# ProPrj_tl494__2025-11-29.net
KiCad netlist of a schematic drawn in EasyEDA Pro
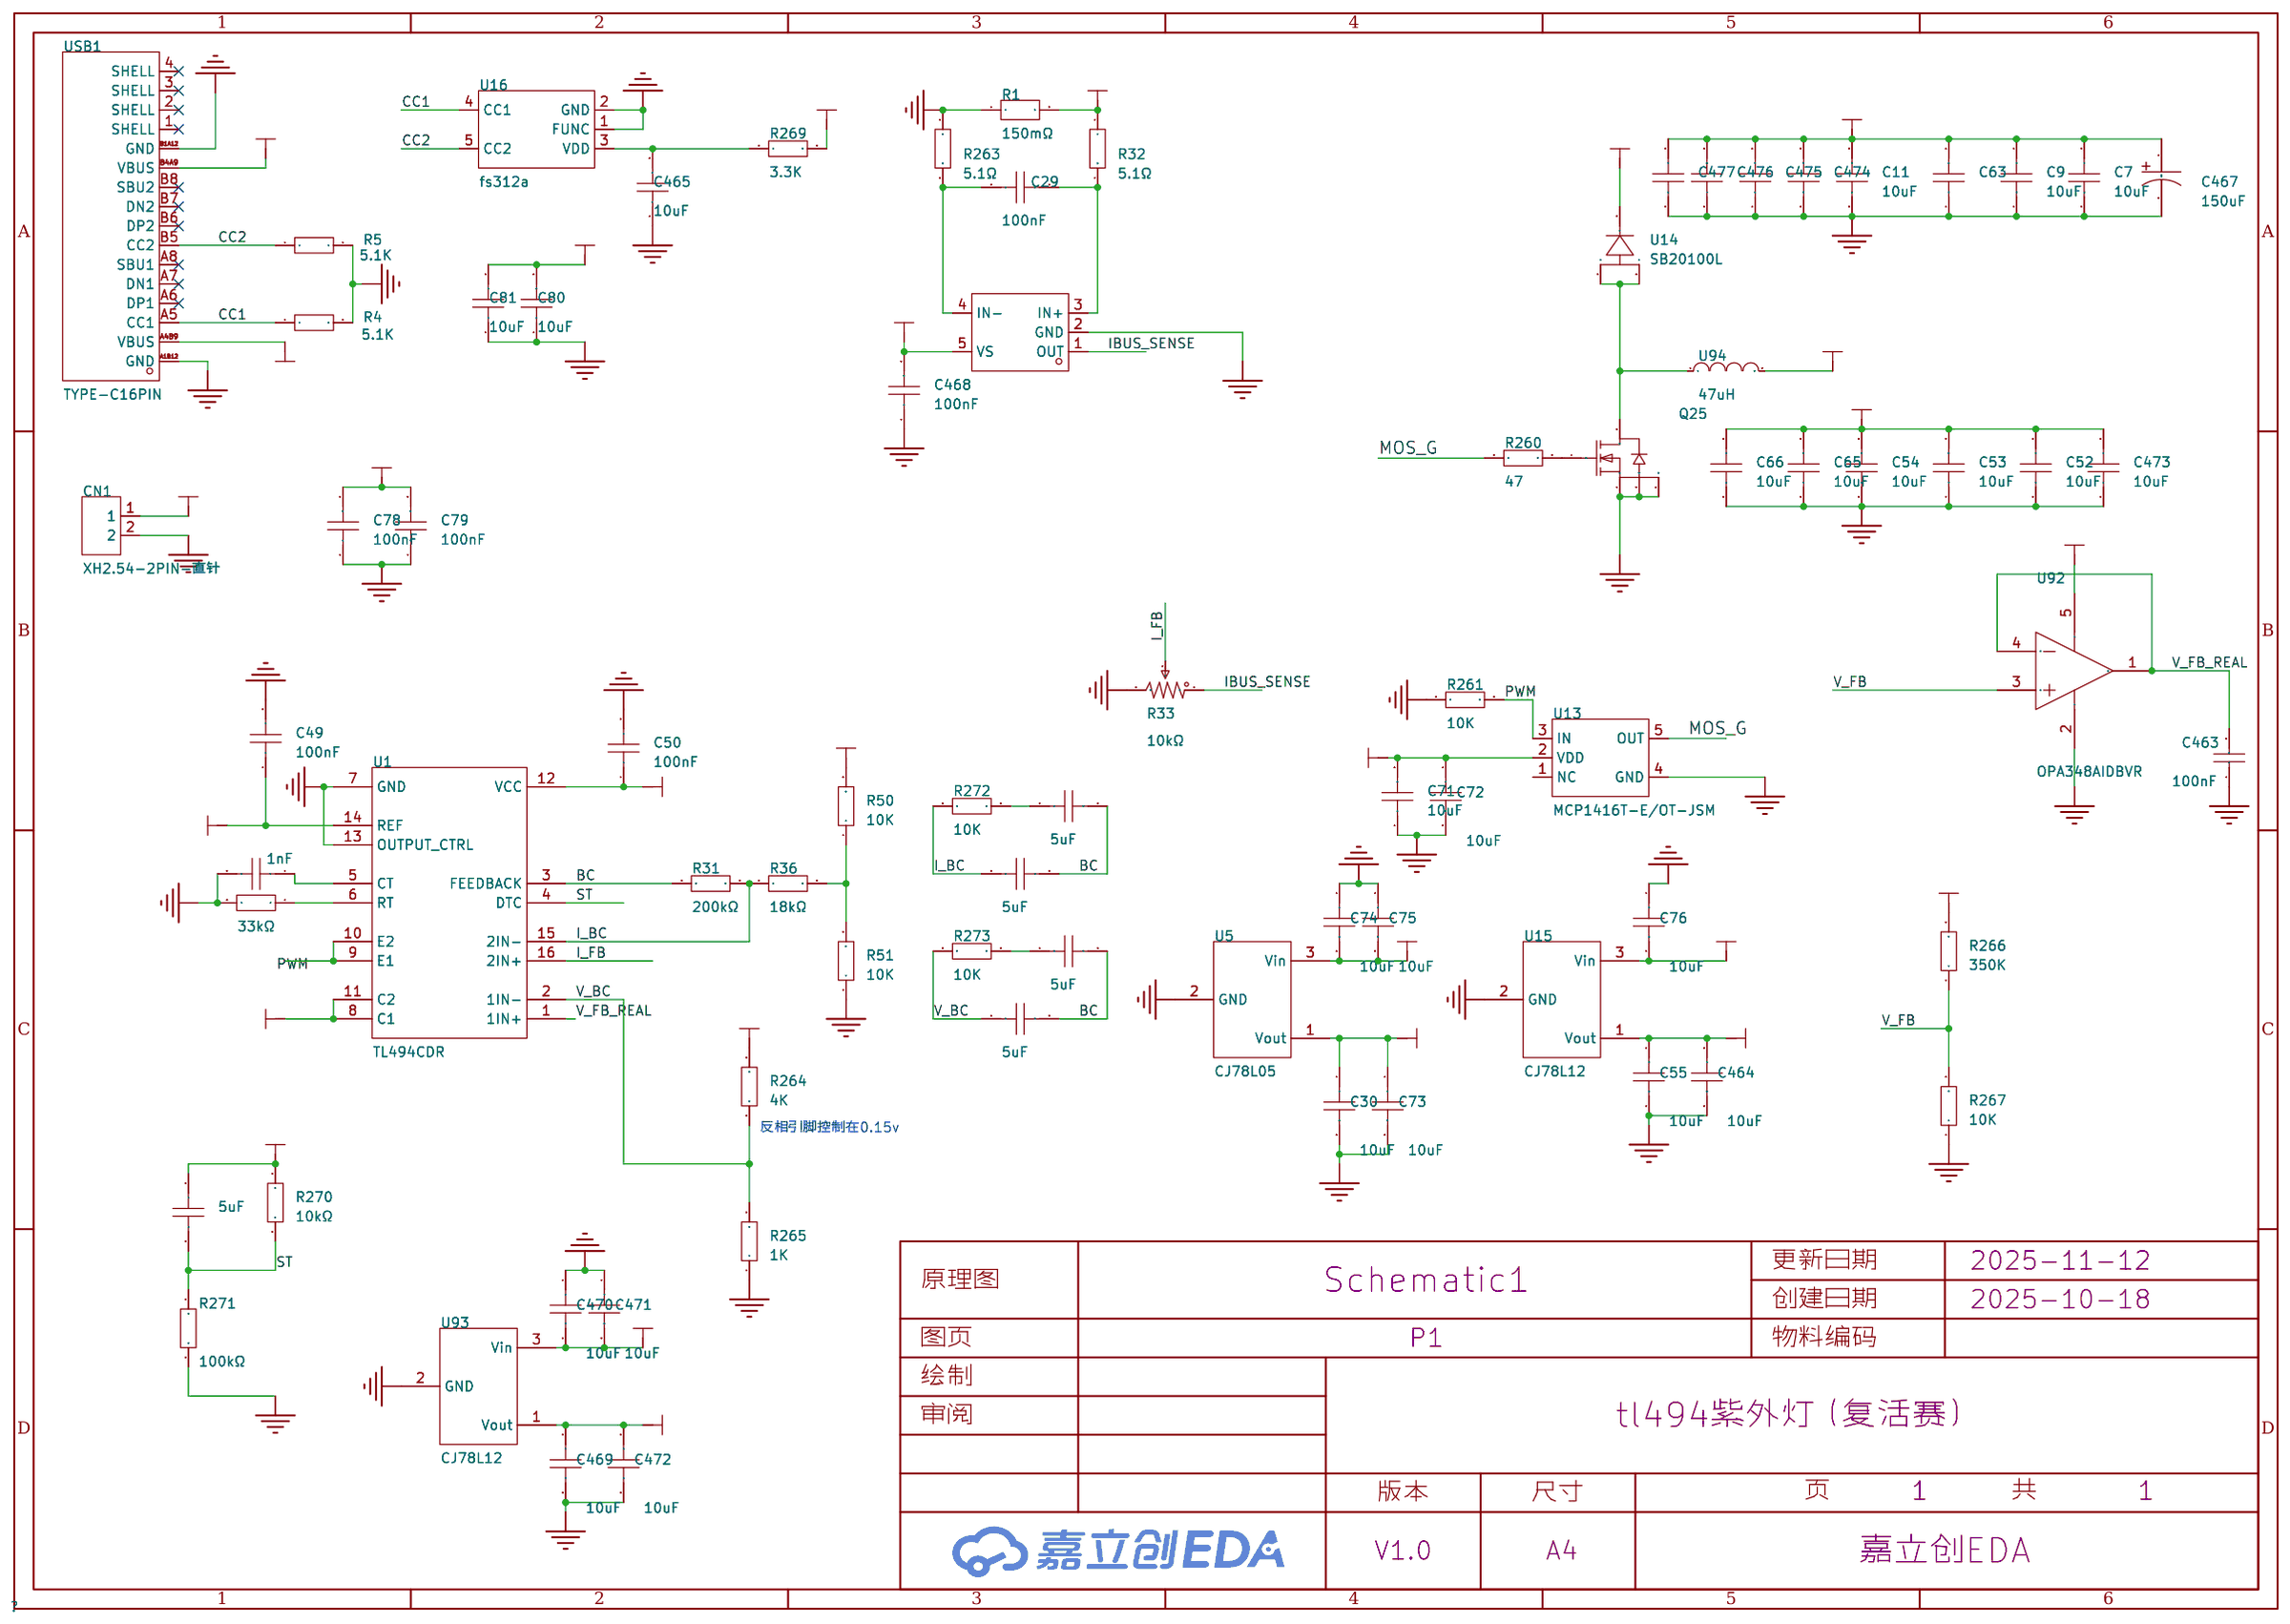
[diagram p0: schematic sheet]

(export (version "E")
  (design (tool "Eeschema 10.0.6"))
  (components
    (comp (ref "C7")
      (value "10uF")
      (footprint "easyedapro:C1210")
      (description "容值:10uF;精度:±10%;额定电压:100V;温度系数:X7R;")
      (fields (field (name "Manufacturer Part") "FS32X106K101EGG") (field (name "Manufacturer") "PSA(信昌电陶)"))
      (libsource (lib "easyedapro") (part "FS32X106K101EGG"))
    )
    (comp (ref "C9")
      (value "10uF")
      (footprint "easyedapro:C1210")
      (description "容值:10uF;精度:±10%;额定电压:100V;温度系数:X7R;")
      (fields (field (name "Manufacturer Part") "FS32X106K101EGG") (field (name "Manufacturer") "PSA(信昌电陶)"))
      (libsource (lib "easyedapro") (part "FS32X106K101EGG"))
    )
    (comp (ref "C11")
      (value "10uF")
      (footprint "easyedapro:C1210")
      (description "容值:10uF;精度:±10%;额定电压:100V;温度系数:X7R;")
      (fields (field (name "Manufacturer Part") "FS32X106K101EGG") (field (name "Manufacturer") "PSA(信昌电陶)"))
      (libsource (lib "easyedapro") (part "FS32X106K101EGG"))
    )
    (comp (ref "C20")
      (value "1nF")
      (footprint "easyedapro:C0603")
      (libsource (lib "easyedapro") (part "CapAcitance"))
    )
    (comp (ref "C29")
      (value "100nF")
      (footprint "easyedapro:C0402")
      (description "容值:100nF;精度:±10%;额定电压:50V;材质(温度系数):X7R;")
      (fields
        (field (name "Manufacturer Part") "CL05B104KB54PNC")
        (field (name "Manufacturer") "SAMSUNG(三星)")
      )
      (libsource (lib "easyedapro") (part "CL05B104KB54PNC"))
    )
    (comp (ref "C30")
      (value "10uF")
      (footprint "easyedapro:C0402")
      (description "容值:100nF;精度:±10%;额定电压:50V;材质(温度系数):X7R;")
      (fields
        (field (name "Manufacturer Part") "CL05B104KB54PNC")
        (field (name "Manufacturer") "SAMSUNG(三星)")
      )
      (libsource (lib "easyedapro") (part "CL05B104KB54PNC"))
    )
    (comp (ref "C49")
      (value "100nF")
      (footprint "easyedapro:C1206")
      (description "容值:220nF;精度:±10%;额定电压:200V;材质(温度系数):X7R;")
      (fields (field (name "Manufacturer Part") "FM31X224K201EEG") (field (name "Manufacturer") "PSA(信昌电陶)"))
      (libsource (lib "easyedapro") (part "FM31X224K201EEG"))
    )
    (comp (ref "C50")
      (value "100nF")
      (footprint "easyedapro:C1206")
      (description "容值:220nF;精度:±10%;额定电压:200V;材质(温度系数):X7R;")
      (fields (field (name "Manufacturer Part") "FM31X224K201EEG") (field (name "Manufacturer") "PSA(信昌电陶)"))
      (libsource (lib "easyedapro") (part "FM31X224K201EEG"))
    )
    (comp (ref "C52")
      (value "10uF")
      (footprint "easyedapro:C1210")
      (description "容值:10uF;精度:±10%;额定电压:100V;温度系数:X7R;")
      (fields (field (name "Manufacturer Part") "FS32X106K101EGG") (field (name "Manufacturer") "PSA(信昌电陶)"))
      (libsource (lib "easyedapro") (part "FS32X106K101EGG"))
    )
    (comp (ref "C53")
      (value "10uF")
      (footprint "easyedapro:C1210")
      (description "容值:10uF;精度:±10%;额定电压:100V;温度系数:X7R;")
      (fields (field (name "Manufacturer Part") "FS32X106K101EGG") (field (name "Manufacturer") "PSA(信昌电陶)"))
      (libsource (lib "easyedapro") (part "FS32X106K101EGG"))
    )
    (comp (ref "C54")
      (value "10uF")
      (footprint "easyedapro:C1210")
      (description "容值:10uF;精度:±10%;额定电压:100V;温度系数:X7R;")
      (fields (field (name "Manufacturer Part") "FS32X106K101EGG") (field (name "Manufacturer") "PSA(信昌电陶)"))
      (libsource (lib "easyedapro") (part "FS32X106K101EGG"))
    )
    (comp (ref "C55")
      (value "10uF")
      (footprint "easyedapro:C0402")
      (description "容值:100nF;精度:±10%;额定电压:50V;材质(温度系数):X7R;")
      (fields
        (field (name "Manufacturer Part") "CL05B104KB54PNC")
        (field (name "Manufacturer") "SAMSUNG(三星)")
      )
      (libsource (lib "easyedapro") (part "CL05B104KB54PNC"))
    )
    (comp (ref "C63")
      (value "10uF")
      (footprint "easyedapro:C1210")
      (description "容值:10uF;精度:±10%;额定电压:100V;温度系数:X7R;")
      (fields (field (name "Manufacturer Part") "FS32X106K101EGG") (field (name "Manufacturer") "PSA(信昌电陶)"))
      (libsource (lib "easyedapro") (part "FS32X106K101EGG"))
    )
    (comp (ref "C65")
      (value "10uF")
      (footprint "easyedapro:C1210")
      (description "容值:10uF;精度:±10%;额定电压:100V;温度系数:X7R;")
      (fields (field (name "Manufacturer Part") "FS32X106K101EGG") (field (name "Manufacturer") "PSA(信昌电陶)"))
      (libsource (lib "easyedapro") (part "FS32X106K101EGG"))
    )
    (comp (ref "C66")
      (value "10uF")
      (footprint "easyedapro:C1210")
      (description "容值:10uF;精度:±10%;额定电压:100V;温度系数:X7R;")
      (fields (field (name "Manufacturer Part") "FS32X106K101EGG") (field (name "Manufacturer") "PSA(信昌电陶)"))
      (libsource (lib "easyedapro") (part "FS32X106K101EGG"))
    )
    (comp (ref "C70")
      (value "5uF")
      (footprint "easyedapro:C0603")
      (libsource (lib "easyedapro") (part "CapAcitance"))
    )
    (comp (ref "C71")
      (value "10uF")
      (footprint "easyedapro:C0402")
      (description "容值:100nF;精度:±10%;额定电压:50V;材质(温度系数):X7R;")
      (fields
        (field (name "Manufacturer Part") "CL05B104KB54PNC")
        (field (name "Manufacturer") "SAMSUNG(三星)")
      )
      (libsource (lib "easyedapro") (part "CL05B104KB54PNC"))
    )
    (comp (ref "C72")
      (value "10uF")
      (footprint "easyedapro:C0402")
      (description "容值:100nF;精度:±10%;额定电压:50V;材质(温度系数):X7R;")
      (fields
        (field (name "Manufacturer Part") "CL05B104KB54PNC")
        (field (name "Manufacturer") "SAMSUNG(三星)")
      )
      (libsource (lib "easyedapro") (part "CL05B104KB54PNC"))
    )
    (comp (ref "C73")
      (value "10uF")
      (footprint "easyedapro:C0402")
      (description "容值:100nF;精度:±10%;额定电压:50V;材质(温度系数):X7R;")
      (fields
        (field (name "Manufacturer Part") "CL05B104KB54PNC")
        (field (name "Manufacturer") "SAMSUNG(三星)")
      )
      (libsource (lib "easyedapro") (part "CL05B104KB54PNC"))
    )
    (comp (ref "C74")
      (value "10uF")
      (footprint "easyedapro:C0402")
      (description "容值:100nF;精度:±10%;额定电压:50V;材质(温度系数):X7R;")
      (fields
        (field (name "Manufacturer Part") "CL05B104KB54PNC")
        (field (name "Manufacturer") "SAMSUNG(三星)")
      )
      (libsource (lib "easyedapro") (part "CL05B104KB54PNC"))
    )
    (comp (ref "C75")
      (value "10uF")
      (footprint "easyedapro:C0402")
      (description "容值:100nF;精度:±10%;额定电压:50V;材质(温度系数):X7R;")
      (fields
        (field (name "Manufacturer Part") "CL05B104KB54PNC")
        (field (name "Manufacturer") "SAMSUNG(三星)")
      )
      (libsource (lib "easyedapro") (part "CL05B104KB54PNC"))
    )
    (comp (ref "C76")
      (value "10uF")
      (footprint "easyedapro:C0402")
      (description "容值:100nF;精度:±10%;额定电压:50V;材质(温度系数):X7R;")
      (fields
        (field (name "Manufacturer Part") "CL05B104KB54PNC")
        (field (name "Manufacturer") "SAMSUNG(三星)")
      )
      (libsource (lib "easyedapro") (part "CL05B104KB54PNC"))
    )
    (comp (ref "C78")
      (value "100nF")
      (footprint "easyedapro:C1206")
      (description "容值:220nF;精度:±10%;额定电压:200V;材质(温度系数):X7R;")
      (fields (field (name "Manufacturer Part") "FM31X224K201EEG") (field (name "Manufacturer") "PSA(信昌电陶)"))
      (libsource (lib "easyedapro") (part "FM31X224K201EEG"))
    )
    (comp (ref "C79")
      (value "100nF")
      (footprint "easyedapro:C1206")
      (description "容值:220nF;精度:±10%;额定电压:200V;材质(温度系数):X7R;")
      (fields (field (name "Manufacturer Part") "FM31X224K201EEG") (field (name "Manufacturer") "PSA(信昌电陶)"))
      (libsource (lib "easyedapro") (part "FM31X224K201EEG"))
    )
    (comp (ref "C80")
      (value "10uF")
      (footprint "easyedapro:C1210")
      (description "容值:10uF;精度:±10%;额定电压:100V;温度系数:X7R;")
      (fields (field (name "Manufacturer Part") "FS32X106K101EGG") (field (name "Manufacturer") "PSA(信昌电陶)"))
      (libsource (lib "easyedapro") (part "FS32X106K101EGG"))
    )
    (comp (ref "C81")
      (value "10uF")
      (footprint "easyedapro:C1210")
      (description "容值:10uF;精度:±10%;额定电压:100V;温度系数:X7R;")
      (fields (field (name "Manufacturer Part") "FS32X106K101EGG") (field (name "Manufacturer") "PSA(信昌电陶)"))
      (libsource (lib "easyedapro") (part "FS32X106K101EGG"))
    )
    (comp (ref "C463")
      (value "100nF")
      (footprint "easyedapro:C0402")
      (description "容值:100nF;精度:±10%;额定电压:16V;材质(温度系数):X7R;")
      (fields
        (field (name "Manufacturer Part") "CL05B104KO5NNNC")
        (field (name "Manufacturer") "SAMSUNG(三星)")
      )
      (libsource (lib "easyedapro") (part "CL05B104KO5NNNC"))
    )
    (comp (ref "C464")
      (value "10uF")
      (footprint "easyedapro:C0402")
      (description "容值:100nF;精度:±10%;额定电压:50V;材质(温度系数):X7R;")
      (fields
        (field (name "Manufacturer Part") "CL05B104KB54PNC")
        (field (name "Manufacturer") "SAMSUNG(三星)")
      )
      (libsource (lib "easyedapro") (part "CL05B104KB54PNC"))
    )
    (comp (ref "C465")
      (value "10uF")
      (footprint "easyedapro:C1210")
      (description "容值:10uF;精度:±10%;额定电压:100V;温度系数:X7R;")
      (fields (field (name "Manufacturer Part") "FS32X106K101EGG") (field (name "Manufacturer") "PSA(信昌电陶)"))
      (libsource (lib "easyedapro") (part "FS32X106K101EGG"))
    )
    (comp (ref "C467")
      (value "150uF")
      (footprint "easyedapro:CAP-TH_BD10.0-P5.00-D1.0-FD")
      (description "容值:150uF;精度:±20%;额定电压:100V;纹波电流:-;等效串联电阻(ESR):-;")
      (fields (field (name "Manufacturer Part") "LKME2002A151MF") (field (name "Manufacturer") "Ymin(永铭)"))
      (libsource (lib "easyedapro") (part "LKME2002A151MF"))
    )
    (comp (ref "C468")
      (value "100nF")
      (footprint "easyedapro:C1206")
      (description "容值:220nF;精度:±10%;额定电压:200V;材质(温度系数):X7R;")
      (fields (field (name "Manufacturer Part") "FM31X224K201EEG") (field (name "Manufacturer") "PSA(信昌电陶)"))
      (libsource (lib "easyedapro") (part "FM31X224K201EEG"))
    )
    (comp (ref "C469")
      (value "10uF")
      (footprint "easyedapro:C0402")
      (description "容值:100nF;精度:±10%;额定电压:50V;材质(温度系数):X7R;")
      (fields
        (field (name "Manufacturer Part") "CL05B104KB54PNC")
        (field (name "Manufacturer") "SAMSUNG(三星)")
      )
      (libsource (lib "easyedapro") (part "CL05B104KB54PNC"))
    )
    (comp (ref "C470")
      (value "10uF")
      (footprint "easyedapro:C0402")
      (description "容值:100nF;精度:±10%;额定电压:50V;材质(温度系数):X7R;")
      (fields
        (field (name "Manufacturer Part") "CL05B104KB54PNC")
        (field (name "Manufacturer") "SAMSUNG(三星)")
      )
      (libsource (lib "easyedapro") (part "CL05B104KB54PNC"))
    )
    (comp (ref "C471")
      (value "10uF")
      (footprint "easyedapro:C0402")
      (description "容值:100nF;精度:±10%;额定电压:50V;材质(温度系数):X7R;")
      (fields
        (field (name "Manufacturer Part") "CL05B104KB54PNC")
        (field (name "Manufacturer") "SAMSUNG(三星)")
      )
      (libsource (lib "easyedapro") (part "CL05B104KB54PNC"))
    )
    (comp (ref "C472")
      (value "10uF")
      (footprint "easyedapro:C0402")
      (description "容值:100nF;精度:±10%;额定电压:50V;材质(温度系数):X7R;")
      (fields
        (field (name "Manufacturer Part") "CL05B104KB54PNC")
        (field (name "Manufacturer") "SAMSUNG(三星)")
      )
      (libsource (lib "easyedapro") (part "CL05B104KB54PNC"))
    )
    (comp (ref "C473")
      (value "10uF")
      (footprint "easyedapro:C1210")
      (description "容值:10uF;精度:±10%;额定电压:100V;温度系数:X7R;")
      (fields (field (name "Manufacturer Part") "FS32X106K101EGG") (field (name "Manufacturer") "PSA(信昌电陶)"))
      (libsource (lib "easyedapro") (part "FS32X106K101EGG"))
    )
    (comp (ref "C474")
      (value "10uF")
      (footprint "easyedapro:C1210")
      (description "容值:10uF;精度:±10%;额定电压:100V;温度系数:X7R;")
      (fields (field (name "Manufacturer Part") "FS32X106K101EGG") (field (name "Manufacturer") "PSA(信昌电陶)"))
      (libsource (lib "easyedapro") (part "FS32X106K101EGG"))
    )
    (comp (ref "C475")
      (value "10uF")
      (footprint "easyedapro:C1210")
      (description "容值:10uF;精度:±10%;额定电压:100V;温度系数:X7R;")
      (fields (field (name "Manufacturer Part") "FS32X106K101EGG") (field (name "Manufacturer") "PSA(信昌电陶)"))
      (libsource (lib "easyedapro") (part "FS32X106K101EGG"))
    )
    (comp (ref "C476")
      (value "10uF")
      (footprint "easyedapro:C1210")
      (description "容值:10uF;精度:±10%;额定电压:100V;温度系数:X7R;")
      (fields (field (name "Manufacturer Part") "FS32X106K101EGG") (field (name "Manufacturer") "PSA(信昌电陶)"))
      (libsource (lib "easyedapro") (part "FS32X106K101EGG"))
    )
    (comp (ref "C477")
      (value "10uF")
      (footprint "easyedapro:C1210")
      (description "容值:10uF;精度:±10%;额定电压:100V;温度系数:X7R;")
      (fields (field (name "Manufacturer Part") "FS32X106K101EGG") (field (name "Manufacturer") "PSA(信昌电陶)"))
      (libsource (lib "easyedapro") (part "FS32X106K101EGG"))
    )
    (comp (ref "C478")
      (value "5uF")
      (footprint "easyedapro:C0603")
      (libsource (lib "easyedapro") (part "CapAcitance"))
    )
    (comp (ref "C479")
      (value "5uF")
      (footprint "easyedapro:C0603")
      (libsource (lib "easyedapro") (part "CapAcitance"))
    )
    (comp (ref "C480")
      (value "5uF")
      (footprint "easyedapro:C0603")
      (libsource (lib "easyedapro") (part "CapAcitance"))
    )
    (comp (ref "C481")
      (value "5uF")
      (footprint "easyedapro:C0603")
      (libsource (lib "easyedapro") (part "CapAcitance"))
    )
    (comp (ref "CN1")
      (value "XH2.54-2PIN-直针")
      (footprint "easyedapro:CONN-TH_XH2.54-2P")
      (libsource (lib "easyedapro") (part "XH2.54-2PIN-直针"))
    )
    (comp (ref "Q25")
      (value "CSD18540Q5B(TOKMAS)")
      (footprint "easyedapro:TDSON-8_L5.9-W5.2-P1.27-BL")
      (description "类型:1个N沟道;漏源电压(Vdss):60V;连续漏极电流(Id):200A;导通电阻(RDS(on)@Vgs,Id):2.3mΩ;功率(Pd):132W;")
      (fields (field (name "Manufacturer") "Tokmas(托克马斯)"))
      (libsource (lib "easyedapro") (part "CSD18540Q5B(TOKMAS)"))
    )
    (comp (ref "R1")
      (value "150mΩ")
      (footprint "easyedapro:R2512")
      (description "电阻类型:采样电阻;阻值:150mΩ;精度:±1%;功率:3W;温度系数:±50ppm/°C;")
      (fields (field (name "Manufacturer Part") "RE2512F3R150") (field (name "Manufacturer") "捷而瑞"))
      (libsource (lib "easyedapro") (part "RE2512F3R150"))
    )
    (comp (ref "R4") (value "5.1K") (footprint "easyedapro:R0603") (libsource (lib "easyedapro") (part "电阻")))
    (comp (ref "R5") (value "5.1K") (footprint "easyedapro:R0603") (libsource (lib "easyedapro") (part "电阻")))
    (comp (ref "R23")
      (value "33kΩ")
      (footprint "easyedapro:Res_1/8W")
      (libsource (lib "easyedapro") (part "电阻"))
    )
    (comp (ref "R31")
      (value "200kΩ")
      (footprint "easyedapro:Res_1/8W")
      (libsource (lib "easyedapro") (part "电阻"))
    )
    (comp (ref "R32")
      (value "5.1Ω")
      (footprint "easyedapro:R0603")
      (description "电阻类型:厚膜电阻;阻值:5.1Ω;精度:±1%;功率:100mW;")
      (fields
        (field (name "Manufacturer Part") "0603WAF510KT5E")
        (field (name "Manufacturer") "UNI-ROYAL(厚声)")
      )
      (libsource (lib "easyedapro") (part "0603WAF510KT5E"))
    )
    (comp (ref "R33")
      (value "10kΩ")
      (footprint "easyedapro:RES-ADJ-TH_3P-L10.0-W10.0-P2.50-L")
      (description "阻值:10kΩ;精度:±10%;")
      (fields (field (name "Manufacturer Part") "3296W-1-103") (field (name "Manufacturer") "BOCHEN(博晨)"))
      (libsource (lib "easyedapro") (part "3296W-1-103"))
    )
    (comp (ref "R36")
      (value "18kΩ")
      (footprint "easyedapro:Res_1/8W")
      (libsource (lib "easyedapro") (part "电阻"))
    )
    (comp (ref "R50")
      (value "10K")
      (footprint "easyedapro:Res_1/8W")
      (libsource (lib "easyedapro") (part "电阻"))
    )
    (comp (ref "R51")
      (value "10K")
      (footprint "easyedapro:Res_1/8W")
      (libsource (lib "easyedapro") (part "电阻"))
    )
    (comp (ref "R260") (value "47") (footprint "easyedapro:R0603") (libsource (lib "easyedapro") (part "电阻")))
    (comp (ref "R261")
      (value "10K")
      (footprint "easyedapro:R0603")
      (libsource (lib "easyedapro") (part "电阻"))
    )
    (comp (ref "R263")
      (value "5.1Ω")
      (footprint "easyedapro:R0603")
      (description "电阻类型:厚膜电阻;阻值:5.1Ω;精度:±1%;功率:100mW;")
      (fields
        (field (name "Manufacturer Part") "0603WAF510KT5E")
        (field (name "Manufacturer") "UNI-ROYAL(厚声)")
      )
      (libsource (lib "easyedapro") (part "0603WAF510KT5E"))
    )
    (comp (ref "R264")
      (value "4K")
      (footprint "easyedapro:Res_1/8W")
      (libsource (lib "easyedapro") (part "电阻"))
    )
    (comp (ref "R265")
      (value "1K")
      (footprint "easyedapro:Res_1/8W")
      (libsource (lib "easyedapro") (part "电阻"))
    )
    (comp (ref "R266")
      (value "350K")
      (footprint "easyedapro:Res_1/8W")
      (libsource (lib "easyedapro") (part "电阻"))
    )
    (comp (ref "R267")
      (value "10K")
      (footprint "easyedapro:Res_1/8W")
      (libsource (lib "easyedapro") (part "电阻"))
    )
    (comp (ref "R269")
      (value "3.3K")
      (footprint "easyedapro:R0603")
      (description "电阻类型:厚膜电阻;阻值:5.1Ω;精度:±1%;功率:100mW;")
      (fields
        (field (name "Manufacturer Part") "0603WAF510KT5E")
        (field (name "Manufacturer") "UNI-ROYAL(厚声)")
      )
      (libsource (lib "easyedapro") (part "0603WAF510KT5E"))
    )
    (comp (ref "R270")
      (value "10kΩ")
      (footprint "easyedapro:Res_1/8W")
      (libsource (lib "easyedapro") (part "电阻"))
    )
    (comp (ref "R271")
      (value "100kΩ")
      (footprint "easyedapro:Res_1/8W")
      (libsource (lib "easyedapro") (part "电阻"))
    )
    (comp (ref "R272")
      (value "10K")
      (footprint "easyedapro:Res_1/8W")
      (libsource (lib "easyedapro") (part "电阻"))
    )
    (comp (ref "R273")
      (value "10K")
      (footprint "easyedapro:Res_1/8W")
      (libsource (lib "easyedapro") (part "电阻"))
    )
    (comp (ref "U1")
      (value "TL494CDR")
      (footprint "easyedapro:SOIC-16_L9.9-W3.9-P1.27-LS6.0-BL")
      (description "功能类型:降压型；升压型；升降压型;输入电压:7V~40V;")
      (fields (field (name "Manufacturer") "TI(德州仪器)"))
      (libsource (lib "easyedapro") (part "TL494CDR"))
    )
    (comp (ref "U4")
      (value "null")
      (footprint "easyedapro:SOT-23-5_L3.0-W1.7-P0.95-LS2.8-BR")
      (description "通道数:1;")
      (fields (field (name "Manufacturer Part") "INA180A2IDBVT") (field (name "Manufacturer") "TI(德州仪器)"))
      (libsource (lib "easyedapro") (part "INA180A2IDBVT"))
    )
    (comp (ref "U5")
      (value "CJ78L05")
      (footprint "easyedapro:SOT-89-3_L4.5-W2.5-P1.50-LS4.2-BR")
      (description "输出类型:固定;工作电压:30V;输出电压:5V;输出电流:100mA;输出极性:正极;")
      (fields (field (name "Manufacturer") "CJ(江苏长电/长晶)"))
      (libsource (lib "easyedapro") (part "CJ78L05"))
    )
    (comp (ref "U13")
      (value "MCP1416T-E/OT-JSM")
      (footprint "easyedapro:SOT-23-5_L3.0-W1.6-P0.95-LS2.8-BR")
      (description "驱动配置:-;负载类型:MOSFET；IGBT;驱动通道数:-;灌电流(IOL):2A;拉电流(IOH):2A;工作电压:4.5V~25V;上升时间(tr):-;下降时间(tf):30ns;")
      (fields (field (name "Manufacturer") "JSMSEMI(杰盛微)"))
      (libsource (lib "easyedapro") (part "MCP1416T-E/OT-JSM"))
    )
    (comp (ref "U14")
      (value "SB20100L")
      (footprint "easyedapro:TO-277_3P-L5.4-W4.0-LS6.5-BR")
      (description "二极管配置:独立式;正向压降(Vf):700mV@20A;直流反向耐压(Vr):100V;整流电流:20A;")
      (fields (field (name "Manufacturer") "GOODWORK(固得沃克)"))
      (libsource (lib "easyedapro") (part "SB20100L_C5807934"))
    )
    (comp (ref "U15")
      (value "CJ78L12")
      (footprint "easyedapro:SOT-89-3_L4.5-W2.5-P1.50-LS4.2-BR")
      (description "输出类型:固定;工作电压:30V;输出电压:5V;输出电流:100mA;输出极性:正极;")
      (fields (field (name "Manufacturer") "CJ(江苏长电/长晶)"))
      (libsource (lib "easyedapro") (part "CJ78L05"))
    )
    (comp (ref "U16")
      (value "fs312a")
      (footprint "easyedapro:SOT-23-5_L3.0-W1.7-P0.95-LS2.8-BL")
      (libsource (lib "easyedapro") (part "FS312A"))
    )
    (comp (ref "U92")
      (value "OPA348AIDBVR")
      (footprint "easyedapro:SOT-23-5_L3.0-W1.7-P0.95-LS2.8-BR")
      (description "放大器数:单路;轨到轨:-;增益带宽积(GBP):1MHz;压摆率(SR):0.5V/us;输入偏置电流(Ib):0.5pA;")
      (fields (field (name "Manufacturer") "TI(德州仪器)"))
      (libsource (lib "easyedapro") (part "OPA348AIDBVR"))
    )
    (comp (ref "U93")
      (value "CJ78L12")
      (footprint "easyedapro:SOT-89-3_L4.5-W2.5-P1.50-LS4.2-BR")
      (description "输出类型:固定;工作电压:30V;输出电压:5V;输出电流:100mA;输出极性:正极;")
      (fields (field (name "Manufacturer") "CJ(江苏长电/长晶)"))
      (libsource (lib "easyedapro") (part "CJ78L05"))
    )
    (comp (ref "U94")
      (value "47uH")
      (footprint "easyedapro:IND-TH_L21.5-W10.0_XR065125T")
      (description "电感值:10uH;精度:±10%;额定电流:7.8A;类型:磁环电感;")
      (fields (field (name "Manufacturer Part") "XR065125TS100MV1L") (field (name "Manufacturer") "XR(祥如)"))
      (libsource (lib "easyedapro") (part "XR065125TS100MV1L"))
    )
    (comp (ref "USB1")
      (value "TYPE-C16PIN")
      (footprint "easyedapro:USB-C-SMD_TYPE-C16PIN")
      (description "连接器类型:Type-C;标准:USB 3.1;公母:母;安装方式:卧贴;触点数量:16P;端口数量:1;额定电流 - 电源:3A;工作温度范围:-40°C~+85°C;")
      (fields (field (name "Manufacturer") "SHOU HAN(首韩)"))
      (libsource (lib "easyedapro") (part "TYPE-C16PIN"))
    )
  )
  (nets
    (net (code "1") (name "+5V") (class "Default")
      (node (ref "C30") (pin "1") (pinfunction "1_1") (pintype "input"))
      (node (ref "C468") (pin "2") (pinfunction "2_2") (pintype "unspecified"))
      (node (ref "C73") (pin "1") (pinfunction "1_1") (pintype "input"))
      (node (ref "U4") (pin "5") (pinfunction "VS_5") (pintype "input"))
      (node (ref "U5") (pin "1") (pinfunction "Vout_1") (pintype "unspecified"))
      (node (ref "U92") (pin "5") (pinfunction "V+_5") (pintype "unspecified"))
    )
    (net (code "2") (name "/BC") (class "Default")
      (node (ref "C478") (pin "2") (pinfunction "2_2") (pintype "input"))
      (node (ref "C479") (pin "2") (pinfunction "2_2") (pintype "input"))
      (node (ref "C480") (pin "2") (pinfunction "2_2") (pintype "input"))
      (node (ref "C481") (pin "2") (pinfunction "2_2") (pintype "input"))
      (node (ref "R31") (pin "1") (pinfunction "1_1") (pintype "input"))
      (node (ref "U1") (pin "3") (pinfunction "FEEDBACK_3") (pintype "unspecified"))
    )
    (net (code "3") (name "/CC1") (class "Default")
      (node (ref "R4") (pin "1") (pinfunction "1_1") (pintype "input"))
      (node (ref "U16") (pin "4") (pinfunction "CC1_4") (pintype "unspecified"))
      (node (ref "USB1") (pin "A5") (pinfunction "CC1_A5") (pintype "unspecified"))
    )
    (net (code "4") (name "/CC2") (class "Default")
      (node (ref "R5") (pin "1") (pinfunction "1_1") (pintype "input"))
      (node (ref "U16") (pin "5") (pinfunction "CC2_5") (pintype "unspecified"))
      (node (ref "USB1") (pin "B5") (pinfunction "CC2_B5") (pintype "unspecified"))
    )
    (net (code "5") (name "/IBUS_SENSE") (class "Default")
      (node (ref "R33") (pin "1") (pinfunction "1_1") (pintype "unspecified"))
      (node (ref "U4") (pin "1") (pinfunction "OUT_1") (pintype "input"))
    )
    (net (code "6") (name "/I_BC") (class "Default")
      (node (ref "C478") (pin "1") (pinfunction "1_1") (pintype "input"))
      (node (ref "R272") (pin "2") (pinfunction "2_2") (pintype "input"))
      (node (ref "R31") (pin "2") (pinfunction "2_2") (pintype "input"))
      (node (ref "R36") (pin "1") (pinfunction "1_1") (pintype "input"))
      (node (ref "U1") (pin "15") (pinfunction "2IN-_15") (pintype "unspecified"))
    )
    (net (code "7") (name "/I_FB") (class "Default")
      (node (ref "R33") (pin "2") (pinfunction "2_2") (pintype "unspecified"))
      (node (ref "U1") (pin "16") (pinfunction "2IN+_16") (pintype "unspecified"))
    )
    (net (code "8") (name "/MOS_G") (class "Default")
      (node (ref "R260") (pin "1") (pinfunction "1_1") (pintype "input"))
      (node (ref "U13") (pin "5") (pinfunction "OUT_5") (pintype "unspecified"))
    )
    (net (code "9") (name "/PWM") (class "Default")
      (node (ref "R261") (pin "2") (pinfunction "2_2") (pintype "input"))
      (node (ref "U1") (pin "10") (pinfunction "E2_10") (pintype "unspecified"))
      (node (ref "U1") (pin "9") (pinfunction "E1_9") (pintype "unspecified"))
      (node (ref "U13") (pin "3") (pinfunction "IN_3") (pintype "unspecified"))
    )
    (net (code "10") (name "/ST") (class "Default")
      (node (ref "C70") (pin "2") (pinfunction "2_2") (pintype "input"))
      (node (ref "R270") (pin "2") (pinfunction "2_2") (pintype "input"))
      (node (ref "R271") (pin "1") (pinfunction "1_1") (pintype "input"))
      (node (ref "U1") (pin "4") (pinfunction "DTC_4") (pintype "unspecified"))
    )
    (net (code "11") (name "/V_BC") (class "Default")
      (node (ref "C480") (pin "1") (pinfunction "1_1") (pintype "input"))
      (node (ref "R264") (pin "1") (pinfunction "1_1") (pintype "input"))
      (node (ref "R265") (pin "2") (pinfunction "2_2") (pintype "input"))
      (node (ref "R273") (pin "2") (pinfunction "2_2") (pintype "input"))
      (node (ref "U1") (pin "2") (pinfunction "1IN-_2") (pintype "unspecified"))
    )
    (net (code "12") (name "/V_FB") (class "Default")
      (node (ref "R266") (pin "1") (pinfunction "1_1") (pintype "input"))
      (node (ref "R267") (pin "2") (pinfunction "2_2") (pintype "input"))
      (node (ref "U92") (pin "3") (pinfunction "IN+_3") (pintype "unspecified"))
    )
    (net (code "13") (name "/V_FB_REAL") (class "Default")
      (node (ref "C463") (pin "2") (pinfunction "2_2") (pintype "input"))
      (node (ref "U1") (pin "1") (pinfunction "1IN+_1") (pintype "unspecified"))
      (node (ref "U92") (pin "1") (pinfunction "OUT_1") (pintype "output"))
      (node (ref "U92") (pin "4") (pinfunction "IN-_4") (pintype "unspecified"))
    )
    (net (code "14") (name "GND") (class "Default")
      (node (ref "C11") (pin "1") (pinfunction "1_1") (pintype "unspecified"))
      (node (ref "C20") (pin "2") (pinfunction "2_2") (pintype "input"))
      (node (ref "C30") (pin "2") (pinfunction "2_2") (pintype "input"))
      (node (ref "C463") (pin "1") (pinfunction "1_1") (pintype "input"))
      (node (ref "C464") (pin "2") (pinfunction "2_2") (pintype "input"))
      (node (ref "C465") (pin "1") (pinfunction "1_1") (pintype "unspecified"))
      (node (ref "C467") (pin "2") (pinfunction "2_2") (pintype "unspecified"))
      (node (ref "C468") (pin "1") (pinfunction "1_1") (pintype "unspecified"))
      (node (ref "C469") (pin "2") (pinfunction "2_2") (pintype "input"))
      (node (ref "C470") (pin "1") (pinfunction "1_1") (pintype "input"))
      (node (ref "C471") (pin "1") (pinfunction "1_1") (pintype "input"))
      (node (ref "C472") (pin "2") (pinfunction "2_2") (pintype "input"))
      (node (ref "C473") (pin "1") (pinfunction "1_1") (pintype "unspecified"))
      (node (ref "C474") (pin "1") (pinfunction "1_1") (pintype "unspecified"))
      (node (ref "C475") (pin "1") (pinfunction "1_1") (pintype "unspecified"))
      (node (ref "C476") (pin "1") (pinfunction "1_1") (pintype "unspecified"))
      (node (ref "C477") (pin "1") (pinfunction "1_1") (pintype "unspecified"))
      (node (ref "C49") (pin "2") (pinfunction "2_2") (pintype "unspecified"))
      (node (ref "C50") (pin "2") (pinfunction "2_2") (pintype "unspecified"))
      (node (ref "C52") (pin "1") (pinfunction "1_1") (pintype "unspecified"))
      (node (ref "C53") (pin "1") (pinfunction "1_1") (pintype "unspecified"))
      (node (ref "C54") (pin "1") (pinfunction "1_1") (pintype "unspecified"))
      (node (ref "C55") (pin "2") (pinfunction "2_2") (pintype "input"))
      (node (ref "C63") (pin "1") (pinfunction "1_1") (pintype "unspecified"))
      (node (ref "C65") (pin "1") (pinfunction "1_1") (pintype "unspecified"))
      (node (ref "C66") (pin "1") (pinfunction "1_1") (pintype "unspecified"))
      (node (ref "C7") (pin "1") (pinfunction "1_1") (pintype "unspecified"))
      (node (ref "C71") (pin "1") (pinfunction "1_1") (pintype "input"))
      (node (ref "C72") (pin "2") (pinfunction "2_2") (pintype "input"))
      (node (ref "C73") (pin "2") (pinfunction "2_2") (pintype "input"))
      (node (ref "C74") (pin "1") (pinfunction "1_1") (pintype "input"))
      (node (ref "C75") (pin "1") (pinfunction "1_1") (pintype "input"))
      (node (ref "C76") (pin "1") (pinfunction "1_1") (pintype "input"))
      (node (ref "C78") (pin "1") (pinfunction "1_1") (pintype "unspecified"))
      (node (ref "C79") (pin "1") (pinfunction "1_1") (pintype "unspecified"))
      (node (ref "C80") (pin "1") (pinfunction "1_1") (pintype "unspecified"))
      (node (ref "C81") (pin "1") (pinfunction "1_1") (pintype "unspecified"))
      (node (ref "C9") (pin "1") (pinfunction "1_1") (pintype "unspecified"))
      (node (ref "CN1") (pin "2") (pinfunction "2_2") (pintype "unspecified"))
      (node (ref "Q25") (pin "1") (pinfunction "S_1") (pintype "unspecified"))
      (node (ref "Q25") (pin "2") (pinfunction "S_2") (pintype "unspecified"))
      (node (ref "Q25") (pin "3") (pinfunction "S_3") (pintype "unspecified"))
      (node (ref "R1") (pin "1") (pinfunction "1_1") (pintype "unspecified"))
      (node (ref "R23") (pin "2") (pinfunction "2_2") (pintype "input"))
      (node (ref "R261") (pin "1") (pinfunction "1_1") (pintype "input"))
      (node (ref "R263") (pin "1") (pinfunction "1_1") (pintype "input"))
      (node (ref "R265") (pin "1") (pinfunction "1_1") (pintype "input"))
      (node (ref "R267") (pin "1") (pinfunction "1_1") (pintype "input"))
      (node (ref "R271") (pin "2") (pinfunction "2_2") (pintype "input"))
      (node (ref "R33") (pin "3") (pinfunction "3_3") (pintype "unspecified"))
      (node (ref "R4") (pin "2") (pinfunction "2_2") (pintype "input"))
      (node (ref "R5") (pin "2") (pinfunction "2_2") (pintype "input"))
      (node (ref "R51") (pin "1") (pinfunction "1_1") (pintype "input"))
      (node (ref "U1") (pin "13") (pinfunction "OUTPUT_CTRL_13") (pintype "unspecified"))
      (node (ref "U1") (pin "7") (pinfunction "GND_7") (pintype "unspecified"))
      (node (ref "U13") (pin "4") (pinfunction "GND_4") (pintype "unspecified"))
      (node (ref "U15") (pin "2") (pinfunction "GND_2") (pintype "unspecified"))
      (node (ref "U16") (pin "1") (pinfunction "FUNC_1") (pintype "unspecified"))
      (node (ref "U16") (pin "2") (pinfunction "GND_2") (pintype "unspecified"))
      (node (ref "U4") (pin "2") (pinfunction "GND_2") (pintype "input"))
      (node (ref "U5") (pin "2") (pinfunction "GND_2") (pintype "unspecified"))
      (node (ref "U92") (pin "2") (pinfunction "V-_2") (pintype "unspecified"))
      (node (ref "U93") (pin "2") (pinfunction "GND_2") (pintype "unspecified"))
      (node (ref "USB1") (pin "A1B12") (pinfunction "GND_A1B12") (pintype "unspecified"))
      (node (ref "USB1") (pin "B1A12") (pinfunction "GND_B1A12") (pintype "unspecified"))
    )
    (net (code "15") (name "GND_LED") (class "Default")
      (node (ref "R1") (pin "2") (pinfunction "2_2") (pintype "unspecified"))
      (node (ref "R32") (pin "1") (pinfunction "1_1") (pintype "input"))
    )
    (net (code "16") (name "Net-(C479-Pad1)") (class "Default")
      (node (ref "C479") (pin "1") (pinfunction "1_1") (pintype "input"))
      (node (ref "R272") (pin "1") (pinfunction "1_1") (pintype "input"))
    )
    (net (code "17") (name "Net-(C481-Pad1)") (class "Default")
      (node (ref "C481") (pin "1") (pinfunction "1_1") (pintype "input"))
      (node (ref "R273") (pin "1") (pinfunction "1_1") (pintype "input"))
    )
    (net (code "18") (name "Net-(Q25-D)") (class "Default")
      (node (ref "Q25") (pin "5") (pinfunction "D_5") (pintype "unspecified"))
      (node (ref "U14") (pin "1") (pinfunction "K_1") (pintype "unspecified"))
      (node (ref "U14") (pin "3") (pinfunction "K_3") (pintype "unspecified"))
      (node (ref "U94") (pin "1") (pinfunction "1_1") (pintype "unspecified"))
    )
    (net (code "19") (name "Net-(Q25-G)") (class "Default")
      (node (ref "Q25") (pin "4") (pinfunction "G_4") (pintype "unspecified"))
      (node (ref "R260") (pin "2") (pinfunction "2_2") (pintype "input"))
    )
    (net (code "20") (name "Net-(R36-Pad2)") (class "Default")
      (node (ref "R36") (pin "2") (pinfunction "2_2") (pintype "input"))
      (node (ref "R50") (pin "1") (pinfunction "1_1") (pintype "input"))
      (node (ref "R51") (pin "2") (pinfunction "2_2") (pintype "input"))
    )
    (net (code "21") (name "Net-(U1-CT)") (class "Default")
      (node (ref "C20") (pin "1") (pinfunction "1_1") (pintype "input"))
      (node (ref "U1") (pin "5") (pinfunction "CT_5") (pintype "unspecified"))
    )
    (net (code "22") (name "Net-(U1-RT)") (class "Default")
      (node (ref "R23") (pin "1") (pinfunction "1_1") (pintype "input"))
      (node (ref "U1") (pin "6") (pinfunction "RT_6") (pintype "unspecified"))
    )
    (net (code "23") (name "Net-(U4-IN+)") (class "Default")
      (node (ref "C29") (pin "2") (pinfunction "2_2") (pintype "input"))
      (node (ref "R32") (pin "2") (pinfunction "2_2") (pintype "input"))
      (node (ref "U4") (pin "3") (pinfunction "IN+_3") (pintype "input"))
    )
    (net (code "24") (name "Net-(U4-IN-)") (class "Default")
      (node (ref "C29") (pin "1") (pinfunction "1_1") (pintype "input"))
      (node (ref "R263") (pin "2") (pinfunction "2_2") (pintype "input"))
      (node (ref "U4") (pin "4") (pinfunction "IN-_4") (pintype "input"))
    )
    (net (code "25") (name "Net-(U16-VDD)") (class "Default")
      (node (ref "C465") (pin "2") (pinfunction "2_2") (pintype "unspecified"))
      (node (ref "R269") (pin "1") (pinfunction "1_1") (pintype "input"))
      (node (ref "U16") (pin "3") (pinfunction "VDD_3") (pintype "unspecified"))
    )
    (net (code "26") (name "REF_5V") (class "Default")
      (node (ref "C49") (pin "1") (pinfunction "1_1") (pintype "unspecified"))
      (node (ref "C70") (pin "1") (pinfunction "1_1") (pintype "input"))
      (node (ref "R264") (pin "2") (pinfunction "2_2") (pintype "input"))
      (node (ref "R270") (pin "1") (pinfunction "1_1") (pintype "input"))
      (node (ref "R50") (pin "2") (pinfunction "2_2") (pintype "input"))
      (node (ref "U1") (pin "11") (pinfunction "C2_11") (pintype "unspecified"))
      (node (ref "U1") (pin "14") (pinfunction "REF_14") (pintype "output"))
      (node (ref "U1") (pin "8") (pinfunction "C1_8") (pintype "unspecified"))
    )
    (net (code "27") (name "VCC_12V") (class "Default")
      (node (ref "C464") (pin "1") (pinfunction "1_1") (pintype "input"))
      (node (ref "C55") (pin "1") (pinfunction "1_1") (pintype "input"))
      (node (ref "C71") (pin "2") (pinfunction "2_2") (pintype "input"))
      (node (ref "C72") (pin "1") (pinfunction "1_1") (pintype "input"))
      (node (ref "U13") (pin "2") (pinfunction "VDD_2") (pintype "unspecified"))
      (node (ref "U15") (pin "1") (pinfunction "Vout_1") (pintype "unspecified"))
    )
    (net (code "28") (name "VCC_12V_0") (class "Default")
      (node (ref "C469") (pin "1") (pinfunction "1_1") (pintype "input"))
      (node (ref "C472") (pin "1") (pinfunction "1_1") (pintype "input"))
      (node (ref "C78") (pin "2") (pinfunction "2_2") (pintype "unspecified"))
      (node (ref "C79") (pin "2") (pinfunction "2_2") (pintype "unspecified"))
      (node (ref "CN1") (pin "1") (pinfunction "1_1") (pintype "unspecified"))
      (node (ref "U93") (pin "1") (pinfunction "Vout_1") (pintype "unspecified"))
    )
    (net (code "29") (name "VCC_20V") (class "Default")
      (node (ref "C470") (pin "2") (pinfunction "2_2") (pintype "input"))
      (node (ref "C471") (pin "2") (pinfunction "2_2") (pintype "input"))
      (node (ref "C473") (pin "2") (pinfunction "2_2") (pintype "unspecified"))
      (node (ref "C50") (pin "1") (pinfunction "1_1") (pintype "unspecified"))
      (node (ref "C52") (pin "2") (pinfunction "2_2") (pintype "unspecified"))
      (node (ref "C53") (pin "2") (pinfunction "2_2") (pintype "unspecified"))
      (node (ref "C54") (pin "2") (pinfunction "2_2") (pintype "unspecified"))
      (node (ref "C65") (pin "2") (pinfunction "2_2") (pintype "unspecified"))
      (node (ref "C66") (pin "2") (pinfunction "2_2") (pintype "unspecified"))
      (node (ref "C74") (pin "2") (pinfunction "2_2") (pintype "input"))
      (node (ref "C75") (pin "2") (pinfunction "2_2") (pintype "input"))
      (node (ref "C76") (pin "2") (pinfunction "2_2") (pintype "input"))
      (node (ref "C80") (pin "2") (pinfunction "2_2") (pintype "unspecified"))
      (node (ref "C81") (pin "2") (pinfunction "2_2") (pintype "unspecified"))
      (node (ref "R269") (pin "2") (pinfunction "2_2") (pintype "input"))
      (node (ref "U1") (pin "12") (pinfunction "VCC_12") (pintype "unspecified"))
      (node (ref "U15") (pin "3") (pinfunction "Vin_3") (pintype "unspecified"))
      (node (ref "U5") (pin "3") (pinfunction "Vin_3") (pintype "unspecified"))
      (node (ref "U93") (pin "3") (pinfunction "Vin_3") (pintype "unspecified"))
      (node (ref "U94") (pin "2") (pinfunction "2_2") (pintype "unspecified"))
      (node (ref "USB1") (pin "A4B9") (pinfunction "VBUS_A4B9") (pintype "unspecified"))
      (node (ref "USB1") (pin "B4A9") (pinfunction "VBUS_B4A9") (pintype "unspecified"))
    )
    (net (code "30") (name "VCC_LED") (class "Default")
      (node (ref "C11") (pin "2") (pinfunction "2_2") (pintype "unspecified"))
      (node (ref "C467") (pin "1") (pinfunction "1_1") (pintype "unspecified"))
      (node (ref "C474") (pin "2") (pinfunction "2_2") (pintype "unspecified"))
      (node (ref "C475") (pin "2") (pinfunction "2_2") (pintype "unspecified"))
      (node (ref "C476") (pin "2") (pinfunction "2_2") (pintype "unspecified"))
      (node (ref "C477") (pin "2") (pinfunction "2_2") (pintype "unspecified"))
      (node (ref "C63") (pin "2") (pinfunction "2_2") (pintype "unspecified"))
      (node (ref "C7") (pin "2") (pinfunction "2_2") (pintype "unspecified"))
      (node (ref "C9") (pin "2") (pinfunction "2_2") (pintype "unspecified"))
      (node (ref "R266") (pin "2") (pinfunction "2_2") (pintype "input"))
      (node (ref "U14") (pin "2") (pinfunction "A_2") (pintype "unspecified"))
    )
    (net (code "31") (name "unconnected-(U13-NC-Pad1)") (class "Default")
      (node (ref "U13") (pin "1") (pinfunction "NC_1") (pintype "unspecified"))
    )
    (net (code "32") (name "unconnected-(USB1-DN1-PadA7)") (class "Default")
      (node (ref "USB1") (pin "A7") (pinfunction "DN1_A7") (pintype "unspecified+no_connect"))
    )
    (net (code "33") (name "unconnected-(USB1-DN2-PadB7)") (class "Default")
      (node (ref "USB1") (pin "B7") (pinfunction "DN2_B7") (pintype "unspecified+no_connect"))
    )
    (net (code "34") (name "unconnected-(USB1-DP1-PadA6)") (class "Default")
      (node (ref "USB1") (pin "A6") (pinfunction "DP1_A6") (pintype "unspecified+no_connect"))
    )
    (net (code "35") (name "unconnected-(USB1-DP2-PadB6)") (class "Default")
      (node (ref "USB1") (pin "B6") (pinfunction "DP2_B6") (pintype "unspecified+no_connect"))
    )
    (net (code "36") (name "unconnected-(USB1-SBU1-PadA8)") (class "Default")
      (node (ref "USB1") (pin "A8") (pinfunction "SBU1_A8") (pintype "unspecified+no_connect"))
    )
    (net (code "37") (name "unconnected-(USB1-SBU2-PadB8)") (class "Default")
      (node (ref "USB1") (pin "B8") (pinfunction "SBU2_B8") (pintype "unspecified+no_connect"))
    )
    (net (code "38") (name "unconnected-(USB1-SHELL-Pad1)") (class "Default")
      (node (ref "USB1") (pin "1") (pinfunction "SHELL_1") (pintype "unspecified+no_connect"))
    )
    (net (code "39") (name "unconnected-(USB1-SHELL-Pad2)") (class "Default")
      (node (ref "USB1") (pin "2") (pinfunction "SHELL_2") (pintype "unspecified+no_connect"))
    )
    (net (code "40") (name "unconnected-(USB1-SHELL-Pad3)") (class "Default")
      (node (ref "USB1") (pin "3") (pinfunction "SHELL_3") (pintype "unspecified+no_connect"))
    )
    (net (code "41") (name "unconnected-(USB1-SHELL-Pad4)") (class "Default")
      (node (ref "USB1") (pin "4") (pinfunction "SHELL_4") (pintype "unspecified+no_connect"))
    )
  )
)
